# ENCODER_Ctrl.net
KiCad netlist of a schematic drawn in Altium Designer
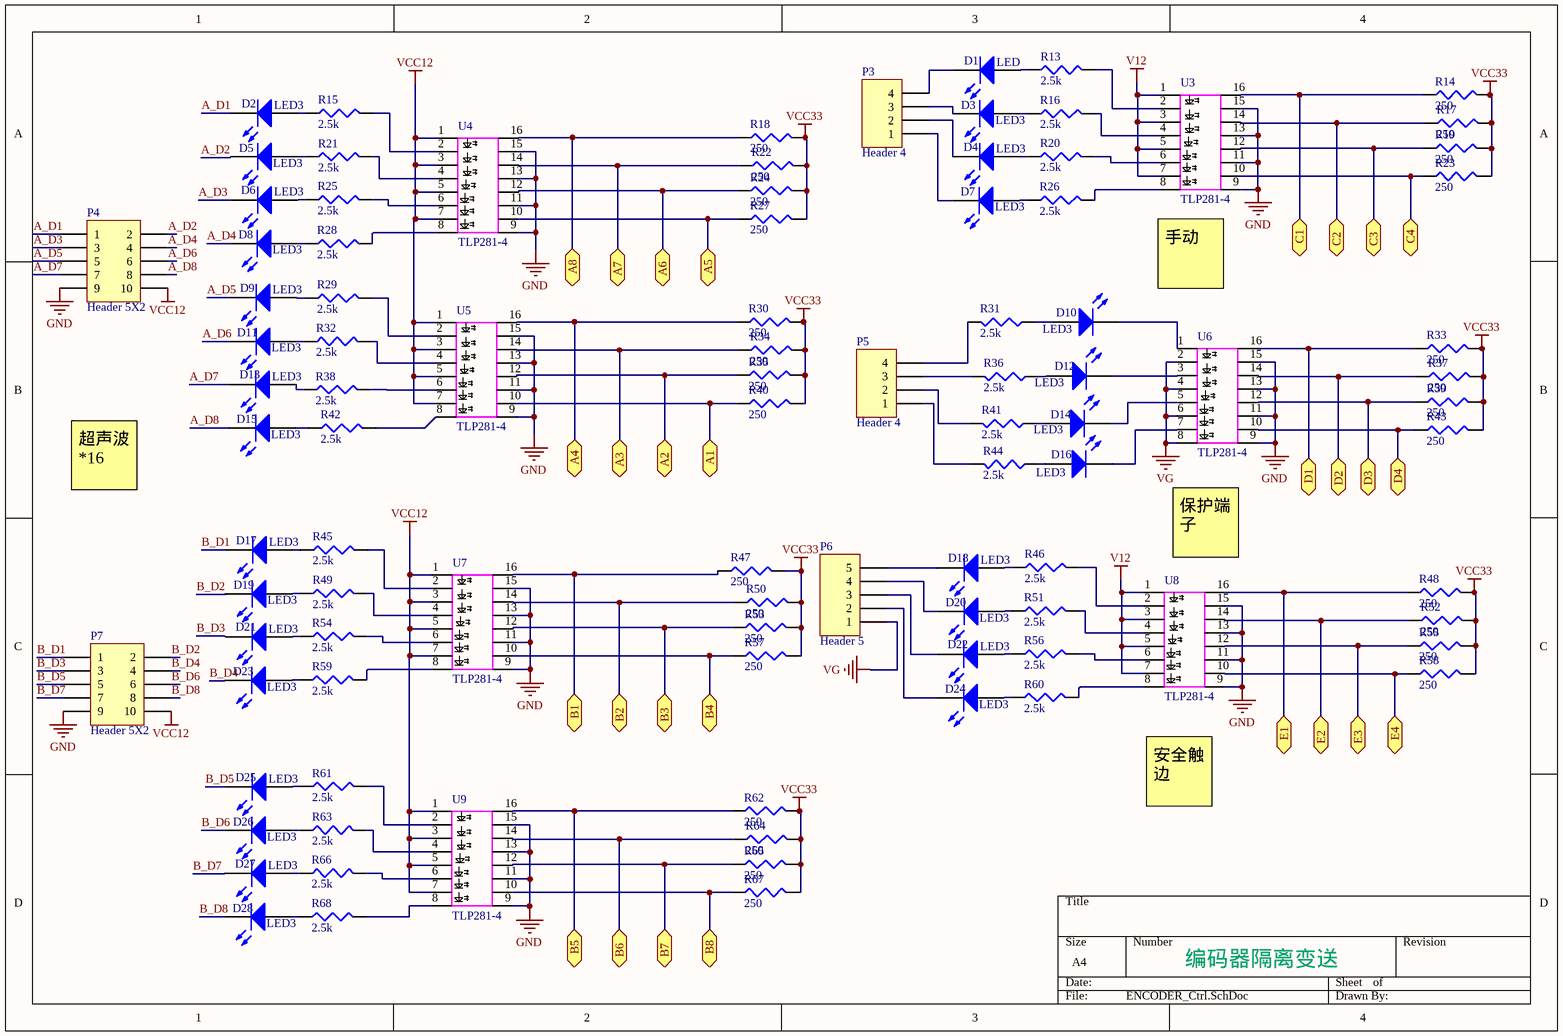
[diagram p0: ENCODER_Ctrl.SchDoc]

(export (version "E")
  (design (tool "Eeschema 10.0.6"))
  (components
    (comp (ref "D1")
      (value "LED")
      (footprint "LED-1206")
      (description "Typical BLUE SiC LED")
      (fields (field (name "PUBLISHER") "Altium Limited"))
      (libsource (lib "Miscellaneous Devices") (part "LED3"))
    )
    (comp (ref "D2")
      (value "LED3")
      (footprint "LED-1206")
      (description "Typical BLUE SiC LED")
      (fields (field (name "PUBLISHER") "Altium Limited"))
      (libsource (lib "Miscellaneous Devices") (part "LED3"))
    )
    (comp (ref "D3")
      (value "LED3")
      (footprint "LED-1206")
      (description "Typical BLUE SiC LED")
      (fields (field (name "PUBLISHER") "Altium Limited"))
      (libsource (lib "Miscellaneous Devices") (part "LED3"))
    )
    (comp (ref "D4")
      (value "LED3")
      (footprint "LED-1206")
      (description "Typical BLUE SiC LED")
      (fields (field (name "PUBLISHER") "Altium Limited"))
      (libsource (lib "Miscellaneous Devices") (part "LED3"))
    )
    (comp (ref "D5")
      (value "LED3")
      (footprint "LED-1206")
      (description "Typical BLUE SiC LED")
      (fields (field (name "PUBLISHER") "Altium Limited"))
      (libsource (lib "Miscellaneous Devices") (part "LED3"))
    )
    (comp (ref "D6")
      (value "LED3")
      (footprint "LED-1206")
      (description "Typical BLUE SiC LED")
      (fields (field (name "PUBLISHER") "Altium Limited"))
      (libsource (lib "Miscellaneous Devices") (part "LED3"))
    )
    (comp (ref "D7")
      (value "LED3")
      (footprint "LED-1206")
      (description "Typical BLUE SiC LED")
      (fields (field (name "PUBLISHER") "Altium Limited"))
      (libsource (lib "Miscellaneous Devices") (part "LED3"))
    )
    (comp (ref "D8")
      (value "LED3")
      (footprint "LED-1206")
      (description "Typical BLUE SiC LED")
      (fields (field (name "PUBLISHER") "Altium Limited"))
      (libsource (lib "Miscellaneous Devices") (part "LED3"))
    )
    (comp (ref "D9")
      (value "LED3")
      (footprint "LED-1206")
      (description "Typical BLUE SiC LED")
      (fields (field (name "PUBLISHER") "Altium Limited"))
      (libsource (lib "Miscellaneous Devices") (part "LED3"))
    )
    (comp (ref "D10")
      (value "LED3")
      (footprint "LED-1206")
      (description "Typical BLUE SiC LED")
      (fields (field (name "PUBLISHER") "Altium Limited"))
      (libsource (lib "Miscellaneous Devices") (part "LED3"))
    )
    (comp (ref "D11")
      (value "LED3")
      (footprint "LED-1206")
      (description "Typical BLUE SiC LED")
      (fields (field (name "PUBLISHER") "Altium Limited"))
      (libsource (lib "Miscellaneous Devices") (part "LED3"))
    )
    (comp (ref "D12")
      (value "LED3")
      (footprint "LED-1206")
      (description "Typical BLUE SiC LED")
      (fields (field (name "PUBLISHER") "Altium Limited"))
      (libsource (lib "Miscellaneous Devices") (part "LED3"))
    )
    (comp (ref "D13")
      (value "LED3")
      (footprint "LED-1206")
      (description "Typical BLUE SiC LED")
      (fields (field (name "PUBLISHER") "Altium Limited"))
      (libsource (lib "Miscellaneous Devices") (part "LED3"))
    )
    (comp (ref "D14")
      (value "LED3")
      (footprint "LED-1206")
      (description "Typical BLUE SiC LED")
      (fields (field (name "PUBLISHER") "Altium Limited"))
      (libsource (lib "Miscellaneous Devices") (part "LED3"))
    )
    (comp (ref "D15")
      (value "LED3")
      (footprint "LED-1206")
      (description "Typical BLUE SiC LED")
      (fields (field (name "PUBLISHER") "Altium Limited"))
      (libsource (lib "Miscellaneous Devices") (part "LED3"))
    )
    (comp (ref "D16")
      (value "LED3")
      (footprint "LED-1206")
      (description "Typical BLUE SiC LED")
      (fields (field (name "PUBLISHER") "Altium Limited"))
      (libsource (lib "Miscellaneous Devices") (part "LED3"))
    )
    (comp (ref "D17")
      (value "LED3")
      (footprint "LED-1206")
      (description "Typical BLUE SiC LED")
      (fields (field (name "PUBLISHER") "Altium Limited"))
      (libsource (lib "Miscellaneous Devices") (part "LED3"))
    )
    (comp (ref "D18")
      (value "LED3")
      (footprint "LED-1206")
      (description "Typical BLUE SiC LED")
      (fields (field (name "PUBLISHER") "Altium Limited"))
      (libsource (lib "Miscellaneous Devices") (part "LED3"))
    )
    (comp (ref "D19")
      (value "LED3")
      (footprint "LED-1206")
      (description "Typical BLUE SiC LED")
      (fields (field (name "PUBLISHER") "Altium Limited"))
      (libsource (lib "Miscellaneous Devices") (part "LED3"))
    )
    (comp (ref "D20")
      (value "LED3")
      (footprint "LED-1206")
      (description "Typical BLUE SiC LED")
      (fields (field (name "PUBLISHER") "Altium Limited"))
      (libsource (lib "Miscellaneous Devices") (part "LED3"))
    )
    (comp (ref "D21")
      (value "LED3")
      (footprint "LED-1206")
      (description "Typical BLUE SiC LED")
      (fields (field (name "PUBLISHER") "Altium Limited"))
      (libsource (lib "Miscellaneous Devices") (part "LED3"))
    )
    (comp (ref "D22")
      (value "LED3")
      (footprint "LED-1206")
      (description "Typical BLUE SiC LED")
      (fields (field (name "PUBLISHER") "Altium Limited"))
      (libsource (lib "Miscellaneous Devices") (part "LED3"))
    )
    (comp (ref "D23")
      (value "LED3")
      (footprint "LED-1206")
      (description "Typical BLUE SiC LED")
      (fields (field (name "PUBLISHER") "Altium Limited"))
      (libsource (lib "Miscellaneous Devices") (part "LED3"))
    )
    (comp (ref "D24")
      (value "LED3")
      (footprint "LED-1206")
      (description "Typical BLUE SiC LED")
      (fields (field (name "PUBLISHER") "Altium Limited"))
      (libsource (lib "Miscellaneous Devices") (part "LED3"))
    )
    (comp (ref "D25")
      (value "LED3")
      (footprint "LED-1206")
      (description "Typical BLUE SiC LED")
      (fields (field (name "PUBLISHER") "Altium Limited"))
      (libsource (lib "Miscellaneous Devices") (part "LED3"))
    )
    (comp (ref "D26")
      (value "LED3")
      (footprint "LED-1206")
      (description "Typical BLUE SiC LED")
      (fields (field (name "PUBLISHER") "Altium Limited"))
      (libsource (lib "Miscellaneous Devices") (part "LED3"))
    )
    (comp (ref "D27")
      (value "LED3")
      (footprint "LED-1206")
      (description "Typical BLUE SiC LED")
      (fields (field (name "PUBLISHER") "Altium Limited"))
      (libsource (lib "Miscellaneous Devices") (part "LED3"))
    )
    (comp (ref "D28")
      (value "LED3")
      (footprint "LED-1206")
      (description "Typical BLUE SiC LED")
      (fields (field (name "PUBLISHER") "Altium Limited"))
      (libsource (lib "Miscellaneous Devices") (part "LED3"))
    )
    (comp (ref "P3")
      (value "Header 4")
      (footprint "3.81-4P")
      (description "Header, 4-Pin")
      (fields (field (name "PUBLISHER") "Altium Limited"))
      (libsource (lib "Miscellaneous Connectors") (part "Header 4"))
    )
    (comp (ref "P4")
      (value "Header 5X2")
      (footprint "HDR2X5")
      (description "Header, 5-Pin, Dual row")
      (fields (field (name "PUBLISHER") "Altium Limited"))
      (libsource (lib "Miscellaneous Connectors") (part "Header 5X2"))
    )
    (comp (ref "P5")
      (value "Header 4")
      (footprint "3.81-4P")
      (description "Header, 4-Pin")
      (fields (field (name "PUBLISHER") "Altium Limited"))
      (libsource (lib "Miscellaneous Connectors") (part "Header 4"))
    )
    (comp (ref "P6")
      (value "Header 5")
      (footprint "3.81-5P")
      (description "Header, 5-Pin")
      (fields (field (name "PUBLISHER") "Altium Limited"))
      (libsource (lib "Miscellaneous Connectors") (part "Header 5"))
    )
    (comp (ref "P7")
      (value "Header 5X2")
      (footprint "HDR2X5")
      (description "Header, 5-Pin, Dual row")
      (fields (field (name "PUBLISHER") "Altium Limited"))
      (libsource (lib "Miscellaneous Connectors") (part "Header 5X2"))
    )
    (comp (ref "R13")
      (value "2.5k")
      (footprint "1206R")
      (description "Resistor")
      (fields (field (name "Comment") "Res3") (field (name "PUBLISHER") "Altium Limited"))
      (libsource (lib "Miscellaneous Devices") (part "Res3"))
    )
    (comp (ref "R14")
      (value "250")
      (footprint "1206R")
      (description "Resistor")
      (fields (field (name "Comment") "Res3") (field (name "PUBLISHER") "Altium Limited"))
      (libsource (lib "Miscellaneous Devices") (part "Res3"))
    )
    (comp (ref "R15")
      (value "2.5k")
      (footprint "1206R")
      (description "Resistor")
      (fields (field (name "Comment") "Res3") (field (name "PUBLISHER") "Altium Limited"))
      (libsource (lib "Miscellaneous Devices") (part "Res3"))
    )
    (comp (ref "R16")
      (value "2.5k")
      (footprint "1206R")
      (description "Resistor")
      (fields (field (name "Comment") "Res3") (field (name "PUBLISHER") "Altium Limited"))
      (libsource (lib "Miscellaneous Devices") (part "Res3"))
    )
    (comp (ref "R17")
      (value "250")
      (footprint "1206R")
      (description "Resistor")
      (fields (field (name "Comment") "Res3") (field (name "PUBLISHER") "Altium Limited"))
      (libsource (lib "Miscellaneous Devices") (part "Res3"))
    )
    (comp (ref "R18")
      (value "250")
      (footprint "1206R")
      (description "Resistor")
      (fields (field (name "Comment") "Res3") (field (name "PUBLISHER") "Altium Limited"))
      (libsource (lib "Miscellaneous Devices") (part "Res3"))
    )
    (comp (ref "R19")
      (value "250")
      (footprint "1206R")
      (description "Resistor")
      (fields (field (name "Comment") "Res3") (field (name "PUBLISHER") "Altium Limited"))
      (libsource (lib "Miscellaneous Devices") (part "Res3"))
    )
    (comp (ref "R20")
      (value "2.5k")
      (footprint "1206R")
      (description "Resistor")
      (fields (field (name "Comment") "Res3") (field (name "PUBLISHER") "Altium Limited"))
      (libsource (lib "Miscellaneous Devices") (part "Res3"))
    )
    (comp (ref "R21")
      (value "2.5k")
      (footprint "1206R")
      (description "Resistor")
      (fields (field (name "Comment") "Res3") (field (name "PUBLISHER") "Altium Limited"))
      (libsource (lib "Miscellaneous Devices") (part "Res3"))
    )
    (comp (ref "R22")
      (value "250")
      (footprint "1206R")
      (description "Resistor")
      (fields (field (name "Comment") "Res3") (field (name "PUBLISHER") "Altium Limited"))
      (libsource (lib "Miscellaneous Devices") (part "Res3"))
    )
    (comp (ref "R23")
      (value "250")
      (footprint "1206R")
      (description "Resistor")
      (fields (field (name "Comment") "Res3") (field (name "PUBLISHER") "Altium Limited"))
      (libsource (lib "Miscellaneous Devices") (part "Res3"))
    )
    (comp (ref "R24")
      (value "250")
      (footprint "1206R")
      (description "Resistor")
      (fields (field (name "Comment") "Res3") (field (name "PUBLISHER") "Altium Limited"))
      (libsource (lib "Miscellaneous Devices") (part "Res3"))
    )
    (comp (ref "R25")
      (value "2.5k")
      (footprint "1206R")
      (description "Resistor")
      (fields (field (name "Comment") "Res3") (field (name "PUBLISHER") "Altium Limited"))
      (libsource (lib "Miscellaneous Devices") (part "Res3"))
    )
    (comp (ref "R26")
      (value "2.5k")
      (footprint "1206R")
      (description "Resistor")
      (fields (field (name "Comment") "Res3") (field (name "PUBLISHER") "Altium Limited"))
      (libsource (lib "Miscellaneous Devices") (part "Res3"))
    )
    (comp (ref "R27")
      (value "250")
      (footprint "1206R")
      (description "Resistor")
      (fields (field (name "Comment") "Res3") (field (name "PUBLISHER") "Altium Limited"))
      (libsource (lib "Miscellaneous Devices") (part "Res3"))
    )
    (comp (ref "R28")
      (value "2.5k")
      (footprint "1206R")
      (description "Resistor")
      (fields (field (name "Comment") "Res3") (field (name "PUBLISHER") "Altium Limited"))
      (libsource (lib "Miscellaneous Devices") (part "Res3"))
    )
    (comp (ref "R29")
      (value "2.5k")
      (footprint "1206R")
      (description "Resistor")
      (fields (field (name "Comment") "Res3") (field (name "PUBLISHER") "Altium Limited"))
      (libsource (lib "Miscellaneous Devices") (part "Res3"))
    )
    (comp (ref "R30")
      (value "250")
      (footprint "1206R")
      (description "Resistor")
      (fields (field (name "Comment") "Res3") (field (name "PUBLISHER") "Altium Limited"))
      (libsource (lib "Miscellaneous Devices") (part "Res3"))
    )
    (comp (ref "R31")
      (value "2.5k")
      (footprint "1206R")
      (description "Resistor")
      (fields (field (name "Comment") "Res3") (field (name "PUBLISHER") "Altium Limited"))
      (libsource (lib "Miscellaneous Devices") (part "Res3"))
    )
    (comp (ref "R32")
      (value "2.5k")
      (footprint "1206R")
      (description "Resistor")
      (fields (field (name "Comment") "Res3") (field (name "PUBLISHER") "Altium Limited"))
      (libsource (lib "Miscellaneous Devices") (part "Res3"))
    )
    (comp (ref "R33")
      (value "250")
      (footprint "1206R")
      (description "Resistor")
      (fields (field (name "Comment") "Res3") (field (name "PUBLISHER") "Altium Limited"))
      (libsource (lib "Miscellaneous Devices") (part "Res3"))
    )
    (comp (ref "R34")
      (value "250")
      (footprint "1206R")
      (description "Resistor")
      (fields (field (name "Comment") "Res3") (field (name "PUBLISHER") "Altium Limited"))
      (libsource (lib "Miscellaneous Devices") (part "Res3"))
    )
    (comp (ref "R35")
      (value "250")
      (footprint "1206R")
      (description "Resistor")
      (fields (field (name "Comment") "Res3") (field (name "PUBLISHER") "Altium Limited"))
      (libsource (lib "Miscellaneous Devices") (part "Res3"))
    )
    (comp (ref "R36")
      (value "2.5k")
      (footprint "1206R")
      (description "Resistor")
      (fields (field (name "Comment") "Res3") (field (name "PUBLISHER") "Altium Limited"))
      (libsource (lib "Miscellaneous Devices") (part "Res3"))
    )
    (comp (ref "R37")
      (value "250")
      (footprint "1206R")
      (description "Resistor")
      (fields (field (name "Comment") "Res3") (field (name "PUBLISHER") "Altium Limited"))
      (libsource (lib "Miscellaneous Devices") (part "Res3"))
    )
    (comp (ref "R38")
      (value "2.5k")
      (footprint "1206R")
      (description "Resistor")
      (fields (field (name "Comment") "Res3") (field (name "PUBLISHER") "Altium Limited"))
      (libsource (lib "Miscellaneous Devices") (part "Res3"))
    )
    (comp (ref "R39")
      (value "250")
      (footprint "1206R")
      (description "Resistor")
      (fields (field (name "Comment") "Res3") (field (name "PUBLISHER") "Altium Limited"))
      (libsource (lib "Miscellaneous Devices") (part "Res3"))
    )
    (comp (ref "R40")
      (value "250")
      (footprint "1206R")
      (description "Resistor")
      (fields (field (name "Comment") "Res3") (field (name "PUBLISHER") "Altium Limited"))
      (libsource (lib "Miscellaneous Devices") (part "Res3"))
    )
    (comp (ref "R41")
      (value "2.5k")
      (footprint "1206R")
      (description "Resistor")
      (fields (field (name "Comment") "Res3") (field (name "PUBLISHER") "Altium Limited"))
      (libsource (lib "Miscellaneous Devices") (part "Res3"))
    )
    (comp (ref "R42")
      (value "2.5k")
      (footprint "1206R")
      (description "Resistor")
      (fields (field (name "Comment") "Res3") (field (name "PUBLISHER") "Altium Limited"))
      (libsource (lib "Miscellaneous Devices") (part "Res3"))
    )
    (comp (ref "R43")
      (value "250")
      (footprint "1206R")
      (description "Resistor")
      (fields (field (name "Comment") "Res3") (field (name "PUBLISHER") "Altium Limited"))
      (libsource (lib "Miscellaneous Devices") (part "Res3"))
    )
    (comp (ref "R44")
      (value "2.5k")
      (footprint "1206R")
      (description "Resistor")
      (fields (field (name "Comment") "Res3") (field (name "PUBLISHER") "Altium Limited"))
      (libsource (lib "Miscellaneous Devices") (part "Res3"))
    )
    (comp (ref "R45")
      (value "2.5k")
      (footprint "1206R")
      (description "Resistor")
      (fields (field (name "Comment") "Res3") (field (name "PUBLISHER") "Altium Limited"))
      (libsource (lib "Miscellaneous Devices") (part "Res3"))
    )
    (comp (ref "R46")
      (value "2.5k")
      (footprint "1206R")
      (description "Resistor")
      (fields (field (name "Comment") "Res3") (field (name "PUBLISHER") "Altium Limited"))
      (libsource (lib "Miscellaneous Devices") (part "Res3"))
    )
    (comp (ref "R47")
      (value "250")
      (footprint "1206R")
      (description "Resistor")
      (fields (field (name "Comment") "Res3") (field (name "PUBLISHER") "Altium Limited"))
      (libsource (lib "Miscellaneous Devices") (part "Res3"))
    )
    (comp (ref "R48")
      (value "250")
      (footprint "1206R")
      (description "Resistor")
      (fields (field (name "Comment") "Res3") (field (name "PUBLISHER") "Altium Limited"))
      (libsource (lib "Miscellaneous Devices") (part "Res3"))
    )
    (comp (ref "R49")
      (value "2.5k")
      (footprint "1206R")
      (description "Resistor")
      (fields (field (name "Comment") "Res3") (field (name "PUBLISHER") "Altium Limited"))
      (libsource (lib "Miscellaneous Devices") (part "Res3"))
    )
    (comp (ref "R50")
      (value "250")
      (footprint "1206R")
      (description "Resistor")
      (fields (field (name "Comment") "Res3") (field (name "PUBLISHER") "Altium Limited"))
      (libsource (lib "Miscellaneous Devices") (part "Res3"))
    )
    (comp (ref "R51")
      (value "2.5k")
      (footprint "1206R")
      (description "Resistor")
      (fields (field (name "Comment") "Res3") (field (name "PUBLISHER") "Altium Limited"))
      (libsource (lib "Miscellaneous Devices") (part "Res3"))
    )
    (comp (ref "R52")
      (value "250")
      (footprint "1206R")
      (description "Resistor")
      (fields (field (name "Comment") "Res3") (field (name "PUBLISHER") "Altium Limited"))
      (libsource (lib "Miscellaneous Devices") (part "Res3"))
    )
    (comp (ref "R53")
      (value "250")
      (footprint "1206R")
      (description "Resistor")
      (fields (field (name "Comment") "Res3") (field (name "PUBLISHER") "Altium Limited"))
      (libsource (lib "Miscellaneous Devices") (part "Res3"))
    )
    (comp (ref "R54")
      (value "2.5k")
      (footprint "1206R")
      (description "Resistor")
      (fields (field (name "Comment") "Res3") (field (name "PUBLISHER") "Altium Limited"))
      (libsource (lib "Miscellaneous Devices") (part "Res3"))
    )
    (comp (ref "R55")
      (value "250")
      (footprint "1206R")
      (description "Resistor")
      (fields (field (name "Comment") "Res3") (field (name "PUBLISHER") "Altium Limited"))
      (libsource (lib "Miscellaneous Devices") (part "Res3"))
    )
    (comp (ref "R56")
      (value "2.5k")
      (footprint "1206R")
      (description "Resistor")
      (fields (field (name "Comment") "Res3") (field (name "PUBLISHER") "Altium Limited"))
      (libsource (lib "Miscellaneous Devices") (part "Res3"))
    )
    (comp (ref "R57")
      (value "250")
      (footprint "1206R")
      (description "Resistor")
      (fields (field (name "Comment") "Res3") (field (name "PUBLISHER") "Altium Limited"))
      (libsource (lib "Miscellaneous Devices") (part "Res3"))
    )
    (comp (ref "R58")
      (value "250")
      (footprint "1206R")
      (description "Resistor")
      (fields (field (name "Comment") "Res3") (field (name "PUBLISHER") "Altium Limited"))
      (libsource (lib "Miscellaneous Devices") (part "Res3"))
    )
    (comp (ref "R59")
      (value "2.5k")
      (footprint "1206R")
      (description "Resistor")
      (fields (field (name "Comment") "Res3") (field (name "PUBLISHER") "Altium Limited"))
      (libsource (lib "Miscellaneous Devices") (part "Res3"))
    )
    (comp (ref "R60")
      (value "2.5k")
      (footprint "1206R")
      (description "Resistor")
      (fields (field (name "Comment") "Res3") (field (name "PUBLISHER") "Altium Limited"))
      (libsource (lib "Miscellaneous Devices") (part "Res3"))
    )
    (comp (ref "R61")
      (value "2.5k")
      (footprint "1206R")
      (description "Resistor")
      (fields (field (name "Comment") "Res3") (field (name "PUBLISHER") "Altium Limited"))
      (libsource (lib "Miscellaneous Devices") (part "Res3"))
    )
    (comp (ref "R62")
      (value "250")
      (footprint "1206R")
      (description "Resistor")
      (fields (field (name "Comment") "Res3") (field (name "PUBLISHER") "Altium Limited"))
      (libsource (lib "Miscellaneous Devices") (part "Res3"))
    )
    (comp (ref "R63")
      (value "2.5k")
      (footprint "1206R")
      (description "Resistor")
      (fields (field (name "Comment") "Res3") (field (name "PUBLISHER") "Altium Limited"))
      (libsource (lib "Miscellaneous Devices") (part "Res3"))
    )
    (comp (ref "R64")
      (value "250")
      (footprint "1206R")
      (description "Resistor")
      (fields (field (name "Comment") "Res3") (field (name "PUBLISHER") "Altium Limited"))
      (libsource (lib "Miscellaneous Devices") (part "Res3"))
    )
    (comp (ref "R65")
      (value "250")
      (footprint "1206R")
      (description "Resistor")
      (fields (field (name "Comment") "Res3") (field (name "PUBLISHER") "Altium Limited"))
      (libsource (lib "Miscellaneous Devices") (part "Res3"))
    )
    (comp (ref "R66")
      (value "2.5k")
      (footprint "1206R")
      (description "Resistor")
      (fields (field (name "Comment") "Res3") (field (name "PUBLISHER") "Altium Limited"))
      (libsource (lib "Miscellaneous Devices") (part "Res3"))
    )
    (comp (ref "R67")
      (value "250")
      (footprint "1206R")
      (description "Resistor")
      (fields (field (name "Comment") "Res3") (field (name "PUBLISHER") "Altium Limited"))
      (libsource (lib "Miscellaneous Devices") (part "Res3"))
    )
    (comp (ref "R68")
      (value "2.5k")
      (footprint "1206R")
      (description "Resistor")
      (fields (field (name "Comment") "Res3") (field (name "PUBLISHER") "Altium Limited"))
      (libsource (lib "Miscellaneous Devices") (part "Res3"))
    )
    (comp (ref "U3")
      (value "TLP281-4")
      (footprint "SO16")
      (libsource (lib "ULN2803APG_SOL18") (part "TLP281-4"))
    )
    (comp (ref "U4")
      (value "TLP281-4")
      (footprint "SO16")
      (libsource (lib "ULN2803APG_SOL18") (part "TLP281-4"))
    )
    (comp (ref "U5")
      (value "TLP281-4")
      (footprint "SO16")
      (libsource (lib "ULN2803APG_SOL18") (part "TLP281-4"))
    )
    (comp (ref "U6")
      (value "TLP281-4")
      (footprint "SO16")
      (libsource (lib "ULN2803APG_SOL18") (part "TLP281-4"))
    )
    (comp (ref "U7")
      (value "TLP281-4")
      (footprint "SO16")
      (libsource (lib "ULN2803APG_SOL18") (part "TLP281-4"))
    )
    (comp (ref "U8")
      (value "TLP281-4")
      (footprint "SO16")
      (libsource (lib "ULN2803APG_SOL18") (part "TLP281-4"))
    )
    (comp (ref "U9")
      (value "TLP281-4")
      (footprint "SO16")
      (libsource (lib "ULN2803APG_SOL18") (part "TLP281-4"))
    )
  )
  (nets
    (net (code "9") (name "/A1") (class "Default")
      (node (ref "R40") (pin "1") (pinfunction "1_1") (pintype "passive"))
      (node (ref "U5") (pin "10") (pintype "passive"))
    )
    (net (code "10") (name "/A2") (class "Default")
      (node (ref "R35") (pin "1") (pinfunction "1_1") (pintype "passive"))
      (node (ref "U5") (pin "12") (pintype "passive"))
    )
    (net (code "11") (name "/A3") (class "Default")
      (node (ref "R34") (pin "1") (pinfunction "1_1") (pintype "passive"))
      (node (ref "U5") (pin "14") (pintype "passive"))
    )
    (net (code "12") (name "/A4") (class "Default")
      (node (ref "R30") (pin "1") (pinfunction "1_1") (pintype "passive"))
      (node (ref "U5") (pin "16") (pintype "passive"))
    )
    (net (code "13") (name "/A5") (class "Default")
      (node (ref "R27") (pin "1") (pinfunction "1_1") (pintype "passive"))
      (node (ref "U4") (pin "10") (pintype "passive"))
    )
    (net (code "14") (name "/A6") (class "Default")
      (node (ref "R24") (pin "1") (pinfunction "1_1") (pintype "passive"))
      (node (ref "U4") (pin "12") (pintype "passive"))
    )
    (net (code "15") (name "/A7") (class "Default")
      (node (ref "R22") (pin "1") (pinfunction "1_1") (pintype "passive"))
      (node (ref "U4") (pin "14") (pintype "passive"))
    )
    (net (code "16") (name "/A8") (class "Default")
      (node (ref "R18") (pin "1") (pinfunction "1_1") (pintype "passive"))
      (node (ref "U4") (pin "16") (pintype "passive"))
    )
    (net (code "17") (name "/A_D1") (class "Default")
      (node (ref "D2") (pin "2") (pinfunction "K_2") (pintype "passive"))
      (node (ref "P4") (pin "1") (pinfunction "1_1") (pintype "passive"))
    )
    (net (code "18") (name "/A_D2") (class "Default")
      (node (ref "D5") (pin "2") (pinfunction "K_2") (pintype "passive"))
      (node (ref "P4") (pin "2") (pinfunction "2_2") (pintype "passive"))
    )
    (net (code "19") (name "/A_D3") (class "Default")
      (node (ref "D6") (pin "2") (pinfunction "K_2") (pintype "passive"))
      (node (ref "P4") (pin "3") (pinfunction "3_3") (pintype "passive"))
    )
    (net (code "20") (name "/A_D4") (class "Default")
      (node (ref "D8") (pin "2") (pinfunction "K_2") (pintype "passive"))
      (node (ref "P4") (pin "4") (pinfunction "4_4") (pintype "passive"))
    )
    (net (code "21") (name "/A_D5") (class "Default")
      (node (ref "D9") (pin "2") (pinfunction "K_2") (pintype "passive"))
      (node (ref "P4") (pin "5") (pinfunction "5_5") (pintype "passive"))
    )
    (net (code "22") (name "/A_D6") (class "Default")
      (node (ref "D11") (pin "2") (pinfunction "K_2") (pintype "passive"))
      (node (ref "P4") (pin "6") (pinfunction "6_6") (pintype "passive"))
    )
    (net (code "23") (name "/A_D7") (class "Default")
      (node (ref "D13") (pin "2") (pinfunction "K_2") (pintype "passive"))
      (node (ref "P4") (pin "7") (pinfunction "7_7") (pintype "passive"))
    )
    (net (code "24") (name "/A_D8") (class "Default")
      (node (ref "D15") (pin "2") (pinfunction "K_2") (pintype "passive"))
      (node (ref "P4") (pin "8") (pinfunction "8_8") (pintype "passive"))
    )
    (net (code "25") (name "/B1") (class "Default")
      (node (ref "R47") (pin "1") (pinfunction "1_1") (pintype "passive"))
      (node (ref "U7") (pin "16") (pintype "passive"))
    )
    (net (code "26") (name "/B2") (class "Default")
      (node (ref "R50") (pin "1") (pinfunction "1_1") (pintype "passive"))
      (node (ref "U7") (pin "14") (pintype "passive"))
    )
    (net (code "27") (name "/B3") (class "Default")
      (node (ref "R53") (pin "1") (pinfunction "1_1") (pintype "passive"))
      (node (ref "U7") (pin "12") (pintype "passive"))
    )
    (net (code "28") (name "/B4") (class "Default")
      (node (ref "R57") (pin "1") (pinfunction "1_1") (pintype "passive"))
      (node (ref "U7") (pin "10") (pintype "passive"))
    )
    (net (code "29") (name "/B5") (class "Default")
      (node (ref "R62") (pin "1") (pinfunction "1_1") (pintype "passive"))
      (node (ref "U9") (pin "16") (pintype "passive"))
    )
    (net (code "30") (name "/B6") (class "Default")
      (node (ref "R64") (pin "1") (pinfunction "1_1") (pintype "passive"))
      (node (ref "U9") (pin "14") (pintype "passive"))
    )
    (net (code "31") (name "/B7") (class "Default")
      (node (ref "R65") (pin "1") (pinfunction "1_1") (pintype "passive"))
      (node (ref "U9") (pin "12") (pintype "passive"))
    )
    (net (code "32") (name "/B8") (class "Default")
      (node (ref "R67") (pin "1") (pinfunction "1_1") (pintype "passive"))
      (node (ref "U9") (pin "10") (pintype "passive"))
    )
    (net (code "33") (name "/B_D1") (class "Default")
      (node (ref "D17") (pin "2") (pinfunction "K_2") (pintype "passive"))
      (node (ref "P7") (pin "1") (pinfunction "1_1") (pintype "passive"))
    )
    (net (code "34") (name "/B_D2") (class "Default")
      (node (ref "D19") (pin "2") (pinfunction "K_2") (pintype "passive"))
      (node (ref "P7") (pin "2") (pinfunction "2_2") (pintype "passive"))
    )
    (net (code "35") (name "/B_D3") (class "Default")
      (node (ref "D21") (pin "2") (pinfunction "K_2") (pintype "passive"))
      (node (ref "P7") (pin "3") (pinfunction "3_3") (pintype "passive"))
    )
    (net (code "36") (name "/B_D4") (class "Default")
      (node (ref "D23") (pin "2") (pinfunction "K_2") (pintype "passive"))
      (node (ref "P7") (pin "4") (pinfunction "4_4") (pintype "passive"))
    )
    (net (code "37") (name "/B_D5") (class "Default")
      (node (ref "D25") (pin "2") (pinfunction "K_2") (pintype "passive"))
      (node (ref "P7") (pin "5") (pinfunction "5_5") (pintype "passive"))
    )
    (net (code "38") (name "/B_D6") (class "Default")
      (node (ref "D26") (pin "2") (pinfunction "K_2") (pintype "passive"))
      (node (ref "P7") (pin "6") (pinfunction "6_6") (pintype "passive"))
    )
    (net (code "39") (name "/B_D7") (class "Default")
      (node (ref "D27") (pin "2") (pinfunction "K_2") (pintype "passive"))
      (node (ref "P7") (pin "7") (pinfunction "7_7") (pintype "passive"))
    )
    (net (code "40") (name "/B_D8") (class "Default")
      (node (ref "D28") (pin "2") (pinfunction "K_2") (pintype "passive"))
      (node (ref "P7") (pin "8") (pinfunction "8_8") (pintype "passive"))
    )
    (net (code "41") (name "/C1") (class "Default")
      (node (ref "R14") (pin "1") (pinfunction "1_1") (pintype "passive"))
      (node (ref "U3") (pin "16") (pintype "passive"))
    )
    (net (code "42") (name "/C2") (class "Default")
      (node (ref "R17") (pin "1") (pinfunction "1_1") (pintype "passive"))
      (node (ref "U3") (pin "14") (pintype "passive"))
    )
    (net (code "43") (name "/C3") (class "Default")
      (node (ref "R19") (pin "1") (pinfunction "1_1") (pintype "passive"))
      (node (ref "U3") (pin "12") (pintype "passive"))
    )
    (net (code "44") (name "/C4") (class "Default")
      (node (ref "R23") (pin "1") (pinfunction "1_1") (pintype "passive"))
      (node (ref "U3") (pin "10") (pintype "passive"))
    )
    (net (code "45") (name "/D1") (class "Default")
      (node (ref "R33") (pin "1") (pinfunction "1_1") (pintype "passive"))
      (node (ref "U6") (pin "16") (pintype "passive"))
    )
    (net (code "46") (name "/D2") (class "Default")
      (node (ref "R37") (pin "1") (pinfunction "1_1") (pintype "passive"))
      (node (ref "U6") (pin "14") (pintype "passive"))
    )
    (net (code "47") (name "/D3") (class "Default")
      (node (ref "R39") (pin "1") (pinfunction "1_1") (pintype "passive"))
      (node (ref "U6") (pin "12") (pintype "passive"))
    )
    (net (code "48") (name "/D4") (class "Default")
      (node (ref "R43") (pin "1") (pinfunction "1_1") (pintype "passive"))
      (node (ref "U6") (pin "10") (pintype "passive"))
    )
    (net (code "49") (name "/E1") (class "Default")
      (node (ref "R48") (pin "1") (pinfunction "1_1") (pintype "passive"))
      (node (ref "U8") (pin "16") (pintype "passive"))
    )
    (net (code "50") (name "/E2") (class "Default")
      (node (ref "R52") (pin "1") (pinfunction "1_1") (pintype "passive"))
      (node (ref "U8") (pin "14") (pintype "passive"))
    )
    (net (code "51") (name "/E3") (class "Default")
      (node (ref "R55") (pin "1") (pinfunction "1_1") (pintype "passive"))
      (node (ref "U8") (pin "12") (pintype "passive"))
    )
    (net (code "52") (name "/E4") (class "Default")
      (node (ref "R58") (pin "1") (pinfunction "1_1") (pintype "passive"))
      (node (ref "U8") (pin "10") (pintype "passive"))
    )
    (net (code "53") (name "GND") (class "Default")
      (node (ref "P4") (pin "9") (pinfunction "9_9") (pintype "passive"))
      (node (ref "P7") (pin "9") (pinfunction "9_9") (pintype "passive"))
      (node (ref "U3") (pin "11") (pintype "passive"))
      (node (ref "U3") (pin "13") (pintype "passive"))
      (node (ref "U3") (pin "15") (pintype "passive"))
      (node (ref "U3") (pin "9") (pintype "passive"))
      (node (ref "U4") (pin "11") (pintype "passive"))
      (node (ref "U4") (pin "13") (pintype "passive"))
      (node (ref "U4") (pin "15") (pintype "passive"))
      (node (ref "U4") (pin "9") (pintype "passive"))
      (node (ref "U5") (pin "11") (pintype "passive"))
      (node (ref "U5") (pin "13") (pintype "passive"))
      (node (ref "U5") (pin "15") (pintype "passive"))
      (node (ref "U5") (pin "9") (pintype "passive"))
      (node (ref "U6") (pin "11") (pintype "passive"))
      (node (ref "U6") (pin "13") (pintype "passive"))
      (node (ref "U6") (pin "15") (pintype "passive"))
      (node (ref "U6") (pin "9") (pintype "passive"))
      (node (ref "U7") (pin "11") (pintype "passive"))
      (node (ref "U7") (pin "13") (pintype "passive"))
      (node (ref "U7") (pin "15") (pintype "passive"))
      (node (ref "U7") (pin "9") (pintype "passive"))
      (node (ref "U8") (pin "11") (pintype "passive"))
      (node (ref "U8") (pin "13") (pintype "passive"))
      (node (ref "U8") (pin "15") (pintype "passive"))
      (node (ref "U8") (pin "9") (pintype "passive"))
      (node (ref "U9") (pin "11") (pintype "passive"))
      (node (ref "U9") (pin "13") (pintype "passive"))
      (node (ref "U9") (pin "15") (pintype "passive"))
      (node (ref "U9") (pin "9") (pintype "passive"))
    )
    (net (code "54") (name "Net-(D1-A)") (class "Default")
      (node (ref "D1") (pin "1") (pinfunction "A_1") (pintype "passive"))
      (node (ref "R13") (pin "1") (pinfunction "1_1") (pintype "passive"))
    )
    (net (code "55") (name "Net-(D1-K)") (class "Default")
      (node (ref "D1") (pin "2") (pinfunction "K_2") (pintype "passive"))
      (node (ref "P3") (pin "4") (pinfunction "4_4") (pintype "passive"))
    )
    (net (code "56") (name "Net-(D2-A)") (class "Default")
      (node (ref "D2") (pin "1") (pinfunction "A_1") (pintype "passive"))
      (node (ref "R15") (pin "1") (pinfunction "1_1") (pintype "passive"))
    )
    (net (code "57") (name "Net-(D3-A)") (class "Default")
      (node (ref "D3") (pin "1") (pinfunction "A_1") (pintype "passive"))
      (node (ref "R16") (pin "1") (pinfunction "1_1") (pintype "passive"))
    )
    (net (code "58") (name "Net-(D3-K)") (class "Default")
      (node (ref "D3") (pin "2") (pinfunction "K_2") (pintype "passive"))
      (node (ref "P3") (pin "3") (pinfunction "3_3") (pintype "passive"))
    )
    (net (code "59") (name "Net-(D4-A)") (class "Default")
      (node (ref "D4") (pin "1") (pinfunction "A_1") (pintype "passive"))
      (node (ref "R20") (pin "1") (pinfunction "1_1") (pintype "passive"))
    )
    (net (code "60") (name "Net-(D4-K)") (class "Default")
      (node (ref "D4") (pin "2") (pinfunction "K_2") (pintype "passive"))
      (node (ref "P3") (pin "2") (pinfunction "2_2") (pintype "passive"))
    )
    (net (code "61") (name "Net-(D5-A)") (class "Default")
      (node (ref "D5") (pin "1") (pinfunction "A_1") (pintype "passive"))
      (node (ref "R21") (pin "1") (pinfunction "1_1") (pintype "passive"))
    )
    (net (code "62") (name "Net-(D6-A)") (class "Default")
      (node (ref "D6") (pin "1") (pinfunction "A_1") (pintype "passive"))
      (node (ref "R25") (pin "1") (pinfunction "1_1") (pintype "passive"))
    )
    (net (code "63") (name "Net-(D7-A)") (class "Default")
      (node (ref "D7") (pin "1") (pinfunction "A_1") (pintype "passive"))
      (node (ref "R26") (pin "1") (pinfunction "1_1") (pintype "passive"))
    )
    (net (code "64") (name "Net-(D7-K)") (class "Default")
      (node (ref "D7") (pin "2") (pinfunction "K_2") (pintype "passive"))
      (node (ref "P3") (pin "1") (pinfunction "1_1") (pintype "passive"))
    )
    (net (code "65") (name "Net-(D8-A)") (class "Default")
      (node (ref "D8") (pin "1") (pinfunction "A_1") (pintype "passive"))
      (node (ref "R28") (pin "1") (pinfunction "1_1") (pintype "passive"))
    )
    (net (code "66") (name "Net-(D9-A)") (class "Default")
      (node (ref "D9") (pin "1") (pinfunction "A_1") (pintype "passive"))
      (node (ref "R29") (pin "1") (pinfunction "1_1") (pintype "passive"))
    )
    (net (code "67") (name "Net-(D10-A)") (class "Default")
      (node (ref "D10") (pin "1") (pinfunction "A_1") (pintype "passive"))
      (node (ref "R31") (pin "1") (pinfunction "1_1") (pintype "passive"))
    )
    (net (code "68") (name "Net-(D10-K)") (class "Default")
      (node (ref "D10") (pin "2") (pinfunction "K_2") (pintype "passive"))
      (node (ref "U6") (pin "1") (pintype "passive"))
    )
    (net (code "69") (name "Net-(D11-A)") (class "Default")
      (node (ref "D11") (pin "1") (pinfunction "A_1") (pintype "passive"))
      (node (ref "R32") (pin "1") (pinfunction "1_1") (pintype "passive"))
    )
    (net (code "70") (name "Net-(D12-A)") (class "Default")
      (node (ref "D12") (pin "1") (pinfunction "A_1") (pintype "passive"))
      (node (ref "R36") (pin "1") (pinfunction "1_1") (pintype "passive"))
    )
    (net (code "71") (name "Net-(D12-K)") (class "Default")
      (node (ref "D12") (pin "2") (pinfunction "K_2") (pintype "passive"))
      (node (ref "U6") (pin "3") (pintype "passive"))
    )
    (net (code "72") (name "Net-(D13-A)") (class "Default")
      (node (ref "D13") (pin "1") (pinfunction "A_1") (pintype "passive"))
      (node (ref "R38") (pin "1") (pinfunction "1_1") (pintype "passive"))
    )
    (net (code "73") (name "Net-(D14-A)") (class "Default")
      (node (ref "D14") (pin "1") (pinfunction "A_1") (pintype "passive"))
      (node (ref "R41") (pin "1") (pinfunction "1_1") (pintype "passive"))
    )
    (net (code "74") (name "Net-(D14-K)") (class "Default")
      (node (ref "D14") (pin "2") (pinfunction "K_2") (pintype "passive"))
      (node (ref "U6") (pin "5") (pintype "passive"))
    )
    (net (code "75") (name "Net-(D15-A)") (class "Default")
      (node (ref "D15") (pin "1") (pinfunction "A_1") (pintype "passive"))
      (node (ref "R42") (pin "1") (pinfunction "1_1") (pintype "passive"))
    )
    (net (code "76") (name "Net-(D16-A)") (class "Default")
      (node (ref "D16") (pin "1") (pinfunction "A_1") (pintype "passive"))
      (node (ref "R44") (pin "1") (pinfunction "1_1") (pintype "passive"))
    )
    (net (code "77") (name "Net-(D16-K)") (class "Default")
      (node (ref "D16") (pin "2") (pinfunction "K_2") (pintype "passive"))
      (node (ref "U6") (pin "7") (pintype "passive"))
    )
    (net (code "78") (name "Net-(D17-A)") (class "Default")
      (node (ref "D17") (pin "1") (pinfunction "A_1") (pintype "passive"))
      (node (ref "R45") (pin "1") (pinfunction "1_1") (pintype "passive"))
    )
    (net (code "79") (name "Net-(D18-A)") (class "Default")
      (node (ref "D18") (pin "1") (pinfunction "A_1") (pintype "passive"))
      (node (ref "R46") (pin "1") (pinfunction "1_1") (pintype "passive"))
    )
    (net (code "80") (name "Net-(D18-K)") (class "Default")
      (node (ref "D18") (pin "2") (pinfunction "K_2") (pintype "passive"))
      (node (ref "P6") (pin "5") (pinfunction "5_5") (pintype "passive"))
    )
    (net (code "81") (name "Net-(D19-A)") (class "Default")
      (node (ref "D19") (pin "1") (pinfunction "A_1") (pintype "passive"))
      (node (ref "R49") (pin "1") (pinfunction "1_1") (pintype "passive"))
    )
    (net (code "82") (name "Net-(D20-A)") (class "Default")
      (node (ref "D20") (pin "1") (pinfunction "A_1") (pintype "passive"))
      (node (ref "R51") (pin "1") (pinfunction "1_1") (pintype "passive"))
    )
    (net (code "83") (name "Net-(D20-K)") (class "Default")
      (node (ref "D20") (pin "2") (pinfunction "K_2") (pintype "passive"))
      (node (ref "P6") (pin "4") (pinfunction "4_4") (pintype "passive"))
    )
    (net (code "84") (name "Net-(D21-A)") (class "Default")
      (node (ref "D21") (pin "1") (pinfunction "A_1") (pintype "passive"))
      (node (ref "R54") (pin "1") (pinfunction "1_1") (pintype "passive"))
    )
    (net (code "85") (name "Net-(D22-A)") (class "Default")
      (node (ref "D22") (pin "1") (pinfunction "A_1") (pintype "passive"))
      (node (ref "R56") (pin "1") (pinfunction "1_1") (pintype "passive"))
    )
    (net (code "86") (name "Net-(D22-K)") (class "Default")
      (node (ref "D22") (pin "2") (pinfunction "K_2") (pintype "passive"))
      (node (ref "P6") (pin "3") (pinfunction "3_3") (pintype "passive"))
    )
    (net (code "87") (name "Net-(D23-A)") (class "Default")
      (node (ref "D23") (pin "1") (pinfunction "A_1") (pintype "passive"))
      (node (ref "R59") (pin "1") (pinfunction "1_1") (pintype "passive"))
    )
    (net (code "88") (name "Net-(D24-A)") (class "Default")
      (node (ref "D24") (pin "1") (pinfunction "A_1") (pintype "passive"))
      (node (ref "R60") (pin "1") (pinfunction "1_1") (pintype "passive"))
    )
    (net (code "89") (name "Net-(D24-K)") (class "Default")
      (node (ref "D24") (pin "2") (pinfunction "K_2") (pintype "passive"))
      (node (ref "P6") (pin "2") (pinfunction "2_2") (pintype "passive"))
    )
    (net (code "90") (name "Net-(D25-A)") (class "Default")
      (node (ref "D25") (pin "1") (pinfunction "A_1") (pintype "passive"))
      (node (ref "R61") (pin "1") (pinfunction "1_1") (pintype "passive"))
    )
    (net (code "91") (name "Net-(D26-A)") (class "Default")
      (node (ref "D26") (pin "1") (pinfunction "A_1") (pintype "passive"))
      (node (ref "R63") (pin "1") (pinfunction "1_1") (pintype "passive"))
    )
    (net (code "92") (name "Net-(D27-A)") (class "Default")
      (node (ref "D27") (pin "1") (pinfunction "A_1") (pintype "passive"))
      (node (ref "R66") (pin "1") (pinfunction "1_1") (pintype "passive"))
    )
    (net (code "93") (name "Net-(D28-A)") (class "Default")
      (node (ref "D28") (pin "1") (pinfunction "A_1") (pintype "passive"))
      (node (ref "R68") (pin "1") (pinfunction "1_1") (pintype "passive"))
    )
    (net (code "94") (name "Net-(P5-Pad1)") (class "Default")
      (node (ref "P5") (pin "1") (pinfunction "1_1") (pintype "passive"))
      (node (ref "R44") (pin "2") (pinfunction "2_2") (pintype "passive"))
    )
    (net (code "95") (name "Net-(P5-Pad2)") (class "Default")
      (node (ref "P5") (pin "2") (pinfunction "2_2") (pintype "passive"))
      (node (ref "R41") (pin "2") (pinfunction "2_2") (pintype "passive"))
    )
    (net (code "96") (name "Net-(P5-Pad3)") (class "Default")
      (node (ref "P5") (pin "3") (pinfunction "3_3") (pintype "passive"))
      (node (ref "R36") (pin "2") (pinfunction "2_2") (pintype "passive"))
    )
    (net (code "97") (name "Net-(P5-Pad4)") (class "Default")
      (node (ref "P5") (pin "4") (pinfunction "4_4") (pintype "passive"))
      (node (ref "R31") (pin "2") (pinfunction "2_2") (pintype "passive"))
    )
    (net (code "98") (name "Net-(R13-Pad2)") (class "Default")
      (node (ref "R13") (pin "2") (pinfunction "2_2") (pintype "passive"))
      (node (ref "U3") (pin "2") (pintype "passive"))
    )
    (net (code "99") (name "Net-(R15-Pad2)") (class "Default")
      (node (ref "R15") (pin "2") (pinfunction "2_2") (pintype "passive"))
      (node (ref "U4") (pin "2") (pintype "passive"))
    )
    (net (code "100") (name "Net-(R16-Pad2)") (class "Default")
      (node (ref "R16") (pin "2") (pinfunction "2_2") (pintype "passive"))
      (node (ref "U3") (pin "4") (pintype "passive"))
    )
    (net (code "101") (name "Net-(R20-Pad2)") (class "Default")
      (node (ref "R20") (pin "2") (pinfunction "2_2") (pintype "passive"))
      (node (ref "U3") (pin "6") (pintype "passive"))
    )
    (net (code "102") (name "Net-(R21-Pad2)") (class "Default")
      (node (ref "R21") (pin "2") (pinfunction "2_2") (pintype "passive"))
      (node (ref "U4") (pin "4") (pintype "passive"))
    )
    (net (code "103") (name "Net-(R25-Pad2)") (class "Default")
      (node (ref "R25") (pin "2") (pinfunction "2_2") (pintype "passive"))
      (node (ref "U4") (pin "6") (pintype "passive"))
    )
    (net (code "104") (name "Net-(R26-Pad2)") (class "Default")
      (node (ref "R26") (pin "2") (pinfunction "2_2") (pintype "passive"))
      (node (ref "U3") (pin "8") (pintype "passive"))
    )
    (net (code "105") (name "Net-(R28-Pad2)") (class "Default")
      (node (ref "R28") (pin "2") (pinfunction "2_2") (pintype "passive"))
      (node (ref "U4") (pin "8") (pintype "passive"))
    )
    (net (code "106") (name "Net-(R29-Pad2)") (class "Default")
      (node (ref "R29") (pin "2") (pinfunction "2_2") (pintype "passive"))
      (node (ref "U5") (pin "2") (pintype "passive"))
    )
    (net (code "107") (name "Net-(R32-Pad2)") (class "Default")
      (node (ref "R32") (pin "2") (pinfunction "2_2") (pintype "passive"))
      (node (ref "U5") (pin "4") (pintype "passive"))
    )
    (net (code "108") (name "Net-(R38-Pad2)") (class "Default")
      (node (ref "R38") (pin "2") (pinfunction "2_2") (pintype "passive"))
      (node (ref "U5") (pin "6") (pintype "passive"))
    )
    (net (code "109") (name "Net-(R42-Pad2)") (class "Default")
      (node (ref "R42") (pin "2") (pinfunction "2_2") (pintype "passive"))
      (node (ref "U5") (pin "8") (pintype "passive"))
    )
    (net (code "110") (name "Net-(R45-Pad2)") (class "Default")
      (node (ref "R45") (pin "2") (pinfunction "2_2") (pintype "passive"))
      (node (ref "U7") (pin "2") (pintype "passive"))
    )
    (net (code "111") (name "Net-(R46-Pad2)") (class "Default")
      (node (ref "R46") (pin "2") (pinfunction "2_2") (pintype "passive"))
      (node (ref "U8") (pin "2") (pintype "passive"))
    )
    (net (code "112") (name "Net-(R49-Pad2)") (class "Default")
      (node (ref "R49") (pin "2") (pinfunction "2_2") (pintype "passive"))
      (node (ref "U7") (pin "4") (pintype "passive"))
    )
    (net (code "113") (name "Net-(R51-Pad2)") (class "Default")
      (node (ref "R51") (pin "2") (pinfunction "2_2") (pintype "passive"))
      (node (ref "U8") (pin "4") (pintype "passive"))
    )
    (net (code "114") (name "Net-(R54-Pad2)") (class "Default")
      (node (ref "R54") (pin "2") (pinfunction "2_2") (pintype "passive"))
      (node (ref "U7") (pin "6") (pintype "passive"))
    )
    (net (code "115") (name "Net-(R56-Pad2)") (class "Default")
      (node (ref "R56") (pin "2") (pinfunction "2_2") (pintype "passive"))
      (node (ref "U8") (pin "6") (pintype "passive"))
    )
    (net (code "116") (name "Net-(R59-Pad2)") (class "Default")
      (node (ref "R59") (pin "2") (pinfunction "2_2") (pintype "passive"))
      (node (ref "U7") (pin "8") (pintype "passive"))
    )
    (net (code "117") (name "Net-(R60-Pad2)") (class "Default")
      (node (ref "R60") (pin "2") (pinfunction "2_2") (pintype "passive"))
      (node (ref "U8") (pin "8") (pintype "passive"))
    )
    (net (code "118") (name "Net-(R61-Pad2)") (class "Default")
      (node (ref "R61") (pin "2") (pinfunction "2_2") (pintype "passive"))
      (node (ref "U9") (pin "2") (pintype "passive"))
    )
    (net (code "119") (name "Net-(R63-Pad2)") (class "Default")
      (node (ref "R63") (pin "2") (pinfunction "2_2") (pintype "passive"))
      (node (ref "U9") (pin "4") (pintype "passive"))
    )
    (net (code "120") (name "Net-(R66-Pad2)") (class "Default")
      (node (ref "R66") (pin "2") (pinfunction "2_2") (pintype "passive"))
      (node (ref "U9") (pin "6") (pintype "passive"))
    )
    (net (code "121") (name "Net-(R68-Pad2)") (class "Default")
      (node (ref "R68") (pin "2") (pinfunction "2_2") (pintype "passive"))
      (node (ref "U9") (pin "8") (pintype "passive"))
    )
    (net (code "122") (name "V12") (class "Default")
      (node (ref "U3") (pin "1") (pintype "passive"))
      (node (ref "U3") (pin "3") (pintype "passive"))
      (node (ref "U3") (pin "5") (pintype "passive"))
      (node (ref "U3") (pin "7") (pintype "passive"))
      (node (ref "U8") (pin "1") (pintype "passive"))
      (node (ref "U8") (pin "3") (pintype "passive"))
      (node (ref "U8") (pin "5") (pintype "passive"))
      (node (ref "U8") (pin "7") (pintype "passive"))
    )
    (net (code "123") (name "VCC12") (class "Default")
      (node (ref "P4") (pin "10") (pinfunction "10_10") (pintype "passive"))
      (node (ref "P7") (pin "10") (pinfunction "10_10") (pintype "passive"))
      (node (ref "U4") (pin "1") (pintype "passive"))
      (node (ref "U4") (pin "3") (pintype "passive"))
      (node (ref "U4") (pin "5") (pintype "passive"))
      (node (ref "U4") (pin "7") (pintype "passive"))
      (node (ref "U5") (pin "1") (pintype "passive"))
      (node (ref "U5") (pin "3") (pintype "passive"))
      (node (ref "U5") (pin "5") (pintype "passive"))
      (node (ref "U5") (pin "7") (pintype "passive"))
      (node (ref "U7") (pin "1") (pintype "passive"))
      (node (ref "U7") (pin "3") (pintype "passive"))
      (node (ref "U7") (pin "5") (pintype "passive"))
      (node (ref "U7") (pin "7") (pintype "passive"))
      (node (ref "U9") (pin "1") (pintype "passive"))
      (node (ref "U9") (pin "3") (pintype "passive"))
      (node (ref "U9") (pin "5") (pintype "passive"))
      (node (ref "U9") (pin "7") (pintype "passive"))
    )
    (net (code "124") (name "VCC33") (class "Default")
      (node (ref "R14") (pin "2") (pinfunction "2_2") (pintype "passive"))
      (node (ref "R17") (pin "2") (pinfunction "2_2") (pintype "passive"))
      (node (ref "R18") (pin "2") (pinfunction "2_2") (pintype "passive"))
      (node (ref "R19") (pin "2") (pinfunction "2_2") (pintype "passive"))
      (node (ref "R22") (pin "2") (pinfunction "2_2") (pintype "passive"))
      (node (ref "R23") (pin "2") (pinfunction "2_2") (pintype "passive"))
      (node (ref "R24") (pin "2") (pinfunction "2_2") (pintype "passive"))
      (node (ref "R27") (pin "2") (pinfunction "2_2") (pintype "passive"))
      (node (ref "R30") (pin "2") (pinfunction "2_2") (pintype "passive"))
      (node (ref "R33") (pin "2") (pinfunction "2_2") (pintype "passive"))
      (node (ref "R34") (pin "2") (pinfunction "2_2") (pintype "passive"))
      (node (ref "R35") (pin "2") (pinfunction "2_2") (pintype "passive"))
      (node (ref "R37") (pin "2") (pinfunction "2_2") (pintype "passive"))
      (node (ref "R39") (pin "2") (pinfunction "2_2") (pintype "passive"))
      (node (ref "R40") (pin "2") (pinfunction "2_2") (pintype "passive"))
      (node (ref "R43") (pin "2") (pinfunction "2_2") (pintype "passive"))
      (node (ref "R47") (pin "2") (pinfunction "2_2") (pintype "passive"))
      (node (ref "R48") (pin "2") (pinfunction "2_2") (pintype "passive"))
      (node (ref "R50") (pin "2") (pinfunction "2_2") (pintype "passive"))
      (node (ref "R52") (pin "2") (pinfunction "2_2") (pintype "passive"))
      (node (ref "R53") (pin "2") (pinfunction "2_2") (pintype "passive"))
      (node (ref "R55") (pin "2") (pinfunction "2_2") (pintype "passive"))
      (node (ref "R57") (pin "2") (pinfunction "2_2") (pintype "passive"))
      (node (ref "R58") (pin "2") (pinfunction "2_2") (pintype "passive"))
      (node (ref "R62") (pin "2") (pinfunction "2_2") (pintype "passive"))
      (node (ref "R64") (pin "2") (pinfunction "2_2") (pintype "passive"))
      (node (ref "R65") (pin "2") (pinfunction "2_2") (pintype "passive"))
      (node (ref "R67") (pin "2") (pinfunction "2_2") (pintype "passive"))
    )
    (net (code "125") (name "VG") (class "Default")
      (node (ref "P6") (pin "1") (pinfunction "1_1") (pintype "passive"))
      (node (ref "U6") (pin "2") (pintype "passive"))
      (node (ref "U6") (pin "4") (pintype "passive"))
      (node (ref "U6") (pin "6") (pintype "passive"))
      (node (ref "U6") (pin "8") (pintype "passive"))
    )
  )
)
